# Sheet1.net
KiCad netlist of a schematic drawn in Altium Designer
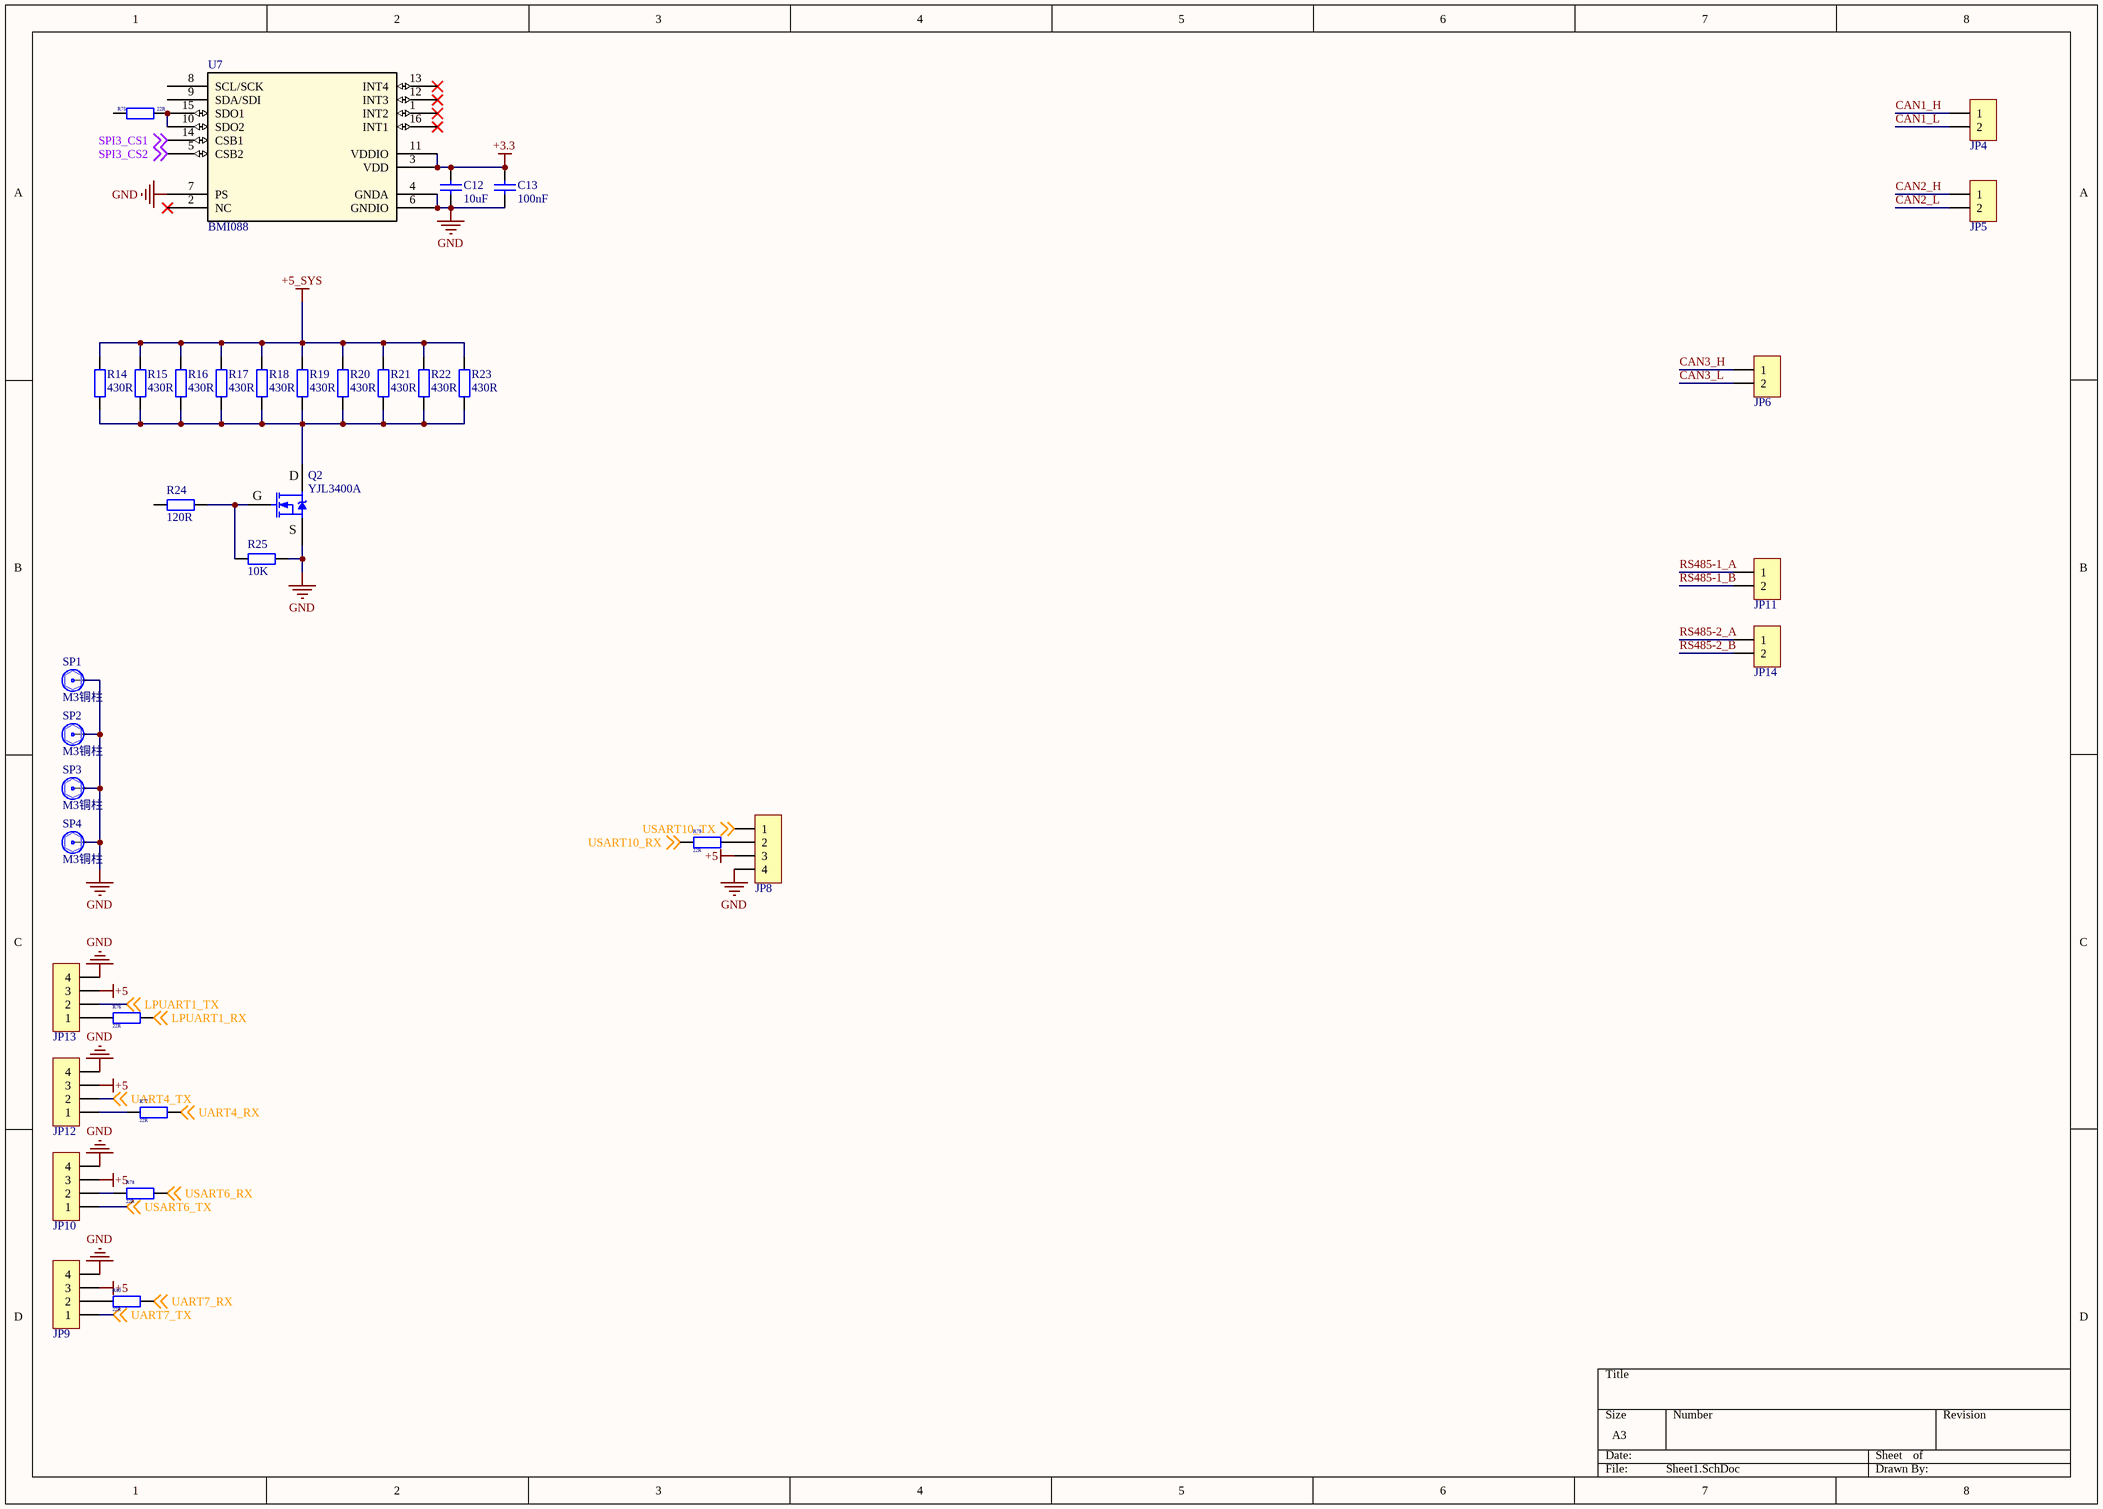
[diagram p0: Sheet1.SchDoc]

(export (version "E")
  (design (tool "Eeschema 10.0.6"))
  (components
    (comp (ref "C12")
      (value "10uF")
      (footprint "C0402_M")
      (description "贴片电容/MLCC电容")
      (libsource (lib "海南大学MECHA战队") (part "C-EDLC"))
    )
    (comp (ref "C13")
      (value "100nF")
      (footprint "C0402_M")
      (description "贴片电容/MLCC电容")
      (libsource (lib "海南大学MECHA战队") (part "C-EDLC"))
    )
    (comp (ref "JP4")
      (value "HDR-1X2")
      (footprint "GH1.25-LT-2P")
      (description "2P连接器")
      (libsource (lib "5.1 - 1.25mm连接器(FPC1.25_GH1.25_MX1.25)") (part "Header 2"))
    )
    (comp (ref "JP5")
      (value "HDR-1X2")
      (footprint "GH1.25-LT-2P")
      (description "2P连接器")
      (libsource (lib "5.1 - 1.25mm连接器(FPC1.25_GH1.25_MX1.25)") (part "Header 2"))
    )
    (comp (ref "JP6")
      (value "HDR-1X2")
      (footprint "GH1.25-LT-2P")
      (description "2P连接器")
      (libsource (lib "5.1 - 1.25mm连接器(FPC1.25_GH1.25_MX1.25)") (part "Header 2"))
    )
    (comp (ref "JP8")
      (value "HDR-1X4")
      (footprint "GH1.25-LT-4P")
      (description "4P连接器")
      (libsource (lib "5.1 - 1.25mm连接器(FPC1.25_GH1.25_MX1.25)") (part "Header 4"))
    )
    (comp (ref "JP9")
      (value "HDR-1X4")
      (footprint "GH1.25-LT-4P")
      (description "4P连接器")
      (libsource (lib "") (part "Header 4_1"))
    )
    (comp (ref "JP10")
      (value "HDR-1X4")
      (footprint "GH1.25-LT-4P")
      (description "4P连接器")
      (libsource (lib "") (part "Header 4_1"))
    )
    (comp (ref "JP11")
      (value "HDR-1X2")
      (footprint "GH1.25-LT-2P")
      (description "2P连接器")
      (libsource (lib "5.1 - 1.25mm连接器(FPC1.25_GH1.25_MX1.25)") (part "Header 2"))
    )
    (comp (ref "JP12")
      (value "HDR-1X4")
      (footprint "GH1.25-LT-4P")
      (description "4P连接器")
      (libsource (lib "") (part "Header 4_1"))
    )
    (comp (ref "JP13")
      (value "HDR-1X4")
      (footprint "GH1.25-LT-4P")
      (description "4P连接器")
      (libsource (lib "") (part "Header 4_1"))
    )
    (comp (ref "JP14")
      (value "HDR-1X2")
      (footprint "GH1.25-LT-2P")
      (description "2P连接器")
      (libsource (lib "5.1 - 1.25mm连接器(FPC1.25_GH1.25_MX1.25)") (part "Header 2"))
    )
    (comp (ref "Q2")
      (value "YJL3400A")
      (footprint "SOT23-3L")
      (description "N沟道 30V/3.16A")
      (libsource (lib "0.4 - 三极管-场效应管-可控硅") (part "SI2306"))
    )
    (comp (ref "R14")
      (value "430R")
      (footprint "R0402_M")
      (description "贴片电阻")
      (libsource (lib "海南大学MECHA战队") (part "R-High Precision"))
    )
    (comp (ref "R15")
      (value "430R")
      (footprint "R0402_M")
      (description "贴片电阻")
      (libsource (lib "海南大学MECHA战队") (part "R-High Precision"))
    )
    (comp (ref "R16")
      (value "430R")
      (footprint "R0402_M")
      (description "贴片电阻")
      (libsource (lib "海南大学MECHA战队") (part "R-High Precision"))
    )
    (comp (ref "R17")
      (value "430R")
      (footprint "R0402_M")
      (description "贴片电阻")
      (libsource (lib "海南大学MECHA战队") (part "R-High Precision"))
    )
    (comp (ref "R18")
      (value "430R")
      (footprint "R0402_M")
      (description "贴片电阻")
      (libsource (lib "海南大学MECHA战队") (part "R-High Precision"))
    )
    (comp (ref "R19")
      (value "430R")
      (footprint "R0402_M")
      (description "贴片电阻")
      (libsource (lib "海南大学MECHA战队") (part "R-High Precision"))
    )
    (comp (ref "R20")
      (value "430R")
      (footprint "R0402_M")
      (description "贴片电阻")
      (libsource (lib "海南大学MECHA战队") (part "R-High Precision"))
    )
    (comp (ref "R21")
      (value "430R")
      (footprint "R0402_M")
      (description "贴片电阻")
      (libsource (lib "海南大学MECHA战队") (part "R-High Precision"))
    )
    (comp (ref "R22")
      (value "430R")
      (footprint "R0402_M")
      (description "贴片电阻")
      (libsource (lib "海南大学MECHA战队") (part "R-High Precision"))
    )
    (comp (ref "R23")
      (value "430R")
      (footprint "R0402_M")
      (description "贴片电阻")
      (libsource (lib "海南大学MECHA战队") (part "R-High Precision"))
    )
    (comp (ref "R24")
      (value "120R")
      (footprint "R0402_M")
      (description "贴片电阻")
      (libsource (lib "海南大学MECHA战队") (part "R-High Precision"))
    )
    (comp (ref "R25")
      (value "10K")
      (footprint "R0402_M")
      (description "贴片电阻")
      (libsource (lib "海南大学MECHA战队") (part "R-High Precision"))
    )
    (comp (ref "R75")
      (value "22R")
      (footprint "R0402_M")
      (description "贴片电阻")
      (libsource (lib "0.1 - 电阻-电容-电感-保险丝-晶振-晶体-磁珠-电位器-法拉电容-馈通电容") (part "R"))
    )
    (comp (ref "R76")
      (value "22R")
      (footprint "R0402_M")
      (description "贴片电阻")
      (libsource (lib "0.1 - 电阻-电容-电感-保险丝-晶振-晶体-磁珠-电位器-法拉电容-馈通电容") (part "R"))
    )
    (comp (ref "R77")
      (value "22R")
      (footprint "R0402_M")
      (description "贴片电阻")
      (libsource (lib "0.1 - 电阻-电容-电感-保险丝-晶振-晶体-磁珠-电位器-法拉电容-馈通电容") (part "R"))
    )
    (comp (ref "R78")
      (value "22R")
      (footprint "R0402_M")
      (description "贴片电阻")
      (libsource (lib "0.1 - 电阻-电容-电感-保险丝-晶振-晶体-磁珠-电位器-法拉电容-馈通电容") (part "R"))
    )
    (comp (ref "R79")
      (value "22R")
      (footprint "R0402_M")
      (description "贴片电阻")
      (libsource (lib "0.1 - 电阻-电容-电感-保险丝-晶振-晶体-磁珠-电位器-法拉电容-馈通电容") (part "R"))
    )
    (comp (ref "R80")
      (value "22R")
      (footprint "R0402_M")
      (description "贴片电阻")
      (libsource (lib "0.1 - 电阻-电容-电感-保险丝-晶振-晶体-磁珠-电位器-法拉电容-馈通电容") (part "R"))
    )
    (comp (ref "SP1")
      (value "M3铜柱")
      (footprint "M3x4+6_N")
      (description "铜柱")
      (libsource (lib "0.5 - 按键_开关_蜂鸣器_电池_测试点_Mark点_铜柱") (part "铜柱加头大焊盘"))
    )
    (comp (ref "SP2")
      (value "M3铜柱")
      (footprint "M3x4+6_N")
      (description "铜柱")
      (libsource (lib "0.5 - 按键_开关_蜂鸣器_电池_测试点_Mark点_铜柱") (part "铜柱加头大焊盘"))
    )
    (comp (ref "SP3")
      (value "M3铜柱")
      (footprint "M3x4+6_N")
      (description "铜柱")
      (libsource (lib "0.5 - 按键_开关_蜂鸣器_电池_测试点_Mark点_铜柱") (part "铜柱加头大焊盘"))
    )
    (comp (ref "SP4")
      (value "M3铜柱")
      (footprint "M3x4+6_N")
      (description "铜柱")
      (libsource (lib "0.5 - 按键_开关_蜂鸣器_电池_测试点_Mark点_铜柱") (part "铜柱加头大焊盘"))
    )
    (comp (ref "U7")
      (value "BMI088")
      (footprint "QFN_BMI085_BOS")
      (description "BMI088 Series 3.6 V 6 Axis Digital Output Accelerometer Motion Sensor - LGA-16")
      (libsource (lib "海南大学MECHA战队") (part "BMI088-Symbol-1"))
    )
  )
  (nets
    (net (code "1") (name "+3.3") (class "Default")
      (node (ref "C12") (pin "1") (pinfunction "1_1") (pintype "passive"))
      (node (ref "C13") (pin "1") (pinfunction "1_1") (pintype "passive"))
      (node (ref "U7") (pin "11") (pinfunction "VDDIO_11") (pintype "power_in"))
      (node (ref "U7") (pin "3") (pinfunction "VDD_3") (pintype "power_in"))
    )
    (net (code "2") (name "+5") (class "Default")
      (node (ref "JP10") (pin "3") (pinfunction "3_3") (pintype "passive"))
      (node (ref "JP12") (pin "3") (pinfunction "3_3") (pintype "passive"))
      (node (ref "JP13") (pin "3") (pinfunction "3_3") (pintype "passive"))
      (node (ref "JP8") (pin "3") (pinfunction "3_3") (pintype "passive"))
      (node (ref "JP9") (pin "3") (pinfunction "3_3") (pintype "passive"))
    )
    (net (code "3") (name "+5_SYS") (class "Default")
      (node (ref "R14") (pin "2") (pinfunction "2_2") (pintype "passive"))
      (node (ref "R15") (pin "2") (pinfunction "2_2") (pintype "passive"))
      (node (ref "R16") (pin "2") (pinfunction "2_2") (pintype "passive"))
      (node (ref "R17") (pin "2") (pinfunction "2_2") (pintype "passive"))
      (node (ref "R18") (pin "2") (pinfunction "2_2") (pintype "passive"))
      (node (ref "R19") (pin "2") (pinfunction "2_2") (pintype "passive"))
      (node (ref "R20") (pin "2") (pinfunction "2_2") (pintype "passive"))
      (node (ref "R21") (pin "2") (pinfunction "2_2") (pintype "passive"))
      (node (ref "R22") (pin "2") (pinfunction "2_2") (pintype "passive"))
      (node (ref "R23") (pin "2") (pinfunction "2_2") (pintype "passive"))
    )
    (net (code "4") (name "/CAN1_H") (class "Default")
      (node (ref "JP4") (pin "1") (pinfunction "1_1") (pintype "passive"))
    )
    (net (code "5") (name "/CAN1_L") (class "Default")
      (node (ref "JP4") (pin "2") (pinfunction "2_2") (pintype "passive"))
    )
    (net (code "6") (name "/CAN2_H") (class "Default")
      (node (ref "JP5") (pin "1") (pinfunction "1_1") (pintype "passive"))
    )
    (net (code "7") (name "/CAN2_L") (class "Default")
      (node (ref "JP5") (pin "2") (pinfunction "2_2") (pintype "passive"))
    )
    (net (code "8") (name "/CAN3_H") (class "Default")
      (node (ref "JP6") (pin "1") (pinfunction "1_1") (pintype "passive"))
    )
    (net (code "9") (name "/CAN3_L") (class "Default")
      (node (ref "JP6") (pin "2") (pinfunction "2_2") (pintype "passive"))
    )
    (net (code "10") (name "/RS485-1_A") (class "Default")
      (node (ref "JP11") (pin "1") (pinfunction "1_1") (pintype "passive"))
    )
    (net (code "11") (name "/RS485-1_B") (class "Default")
      (node (ref "JP11") (pin "2") (pinfunction "2_2") (pintype "passive"))
    )
    (net (code "12") (name "/RS485-2_A") (class "Default")
      (node (ref "JP14") (pin "1") (pinfunction "1_1") (pintype "passive"))
    )
    (net (code "13") (name "/RS485-2_B") (class "Default")
      (node (ref "JP14") (pin "2") (pinfunction "2_2") (pintype "passive"))
    )
    (net (code "14") (name "GND") (class "Default")
      (node (ref "C12") (pin "2") (pinfunction "2_2") (pintype "passive"))
      (node (ref "C13") (pin "2") (pinfunction "2_2") (pintype "passive"))
      (node (ref "JP10") (pin "4") (pinfunction "4_4") (pintype "passive"))
      (node (ref "JP12") (pin "4") (pinfunction "4_4") (pintype "passive"))
      (node (ref "JP13") (pin "4") (pinfunction "4_4") (pintype "passive"))
      (node (ref "JP8") (pin "4") (pinfunction "4_4") (pintype "passive"))
      (node (ref "JP9") (pin "4") (pinfunction "4_4") (pintype "passive"))
      (node (ref "Q2") (pin "2") (pinfunction "S_2") (pintype "passive"))
      (node (ref "R25") (pin "1") (pinfunction "1_1") (pintype "passive"))
      (node (ref "SP1") (pin "1") (pinfunction "1_1") (pintype "passive"))
      (node (ref "SP2") (pin "1") (pinfunction "1_1") (pintype "passive"))
      (node (ref "SP3") (pin "1") (pinfunction "1_1") (pintype "passive"))
      (node (ref "SP4") (pin "1") (pinfunction "1_1") (pintype "passive"))
      (node (ref "U7") (pin "4") (pinfunction "GNDA_4") (pintype "power_in"))
      (node (ref "U7") (pin "6") (pinfunction "GNDIO_6") (pintype "power_in"))
      (node (ref "U7") (pin "7") (pinfunction "PS_7") (pintype "passive"))
    )
    (net (code "15") (name "LPUART1_RX") (class "Default")
      (node (ref "R76") (pin "2") (pinfunction "2_2") (pintype "passive"))
    )
    (net (code "16") (name "LPUART1_TX") (class "Default")
      (node (ref "JP13") (pin "2") (pinfunction "2_2") (pintype "passive"))
    )
    (net (code "17") (name "Net-(JP8-Pad2)") (class "Default")
      (node (ref "JP8") (pin "2") (pinfunction "2_2") (pintype "passive"))
      (node (ref "R79") (pin "2") (pinfunction "2_2") (pintype "passive"))
    )
    (net (code "18") (name "Net-(JP9-Pad2)") (class "Default")
      (node (ref "JP9") (pin "2") (pinfunction "2_2") (pintype "passive"))
      (node (ref "R80") (pin "1") (pinfunction "1_1") (pintype "passive"))
    )
    (net (code "19") (name "Net-(JP10-Pad2)") (class "Default")
      (node (ref "JP10") (pin "2") (pinfunction "2_2") (pintype "passive"))
      (node (ref "R78") (pin "1") (pinfunction "1_1") (pintype "passive"))
    )
    (net (code "20") (name "Net-(JP12-Pad1)") (class "Default")
      (node (ref "JP12") (pin "1") (pinfunction "1_1") (pintype "passive"))
      (node (ref "R77") (pin "1") (pinfunction "1_1") (pintype "passive"))
    )
    (net (code "21") (name "Net-(JP13-Pad1)") (class "Default")
      (node (ref "JP13") (pin "1") (pinfunction "1_1") (pintype "passive"))
      (node (ref "R76") (pin "1") (pinfunction "1_1") (pintype "passive"))
    )
    (net (code "22") (name "Net-(Q2-D)") (class "Default")
      (node (ref "Q2") (pin "3") (pinfunction "D_3") (pintype "passive"))
      (node (ref "R14") (pin "1") (pinfunction "1_1") (pintype "passive"))
      (node (ref "R15") (pin "1") (pinfunction "1_1") (pintype "passive"))
      (node (ref "R16") (pin "1") (pinfunction "1_1") (pintype "passive"))
      (node (ref "R17") (pin "1") (pinfunction "1_1") (pintype "passive"))
      (node (ref "R18") (pin "1") (pinfunction "1_1") (pintype "passive"))
      (node (ref "R19") (pin "1") (pinfunction "1_1") (pintype "passive"))
      (node (ref "R20") (pin "1") (pinfunction "1_1") (pintype "passive"))
      (node (ref "R21") (pin "1") (pinfunction "1_1") (pintype "passive"))
      (node (ref "R22") (pin "1") (pinfunction "1_1") (pintype "passive"))
      (node (ref "R23") (pin "1") (pinfunction "1_1") (pintype "passive"))
    )
    (net (code "23") (name "Net-(Q2-G)") (class "Default")
      (node (ref "Q2") (pin "1") (pinfunction "G_1") (pintype "passive"))
      (node (ref "R24") (pin "1") (pinfunction "1_1") (pintype "passive"))
      (node (ref "R25") (pin "2") (pinfunction "2_2") (pintype "passive"))
    )
    (net (code "24") (name "Net-(U7-SDO1)") (class "Default")
      (node (ref "R75") (pin "1") (pinfunction "1_1") (pintype "passive"))
      (node (ref "U7") (pin "10") (pinfunction "SDO2_10") (pintype "bidirectional"))
      (node (ref "U7") (pin "15") (pinfunction "SDO1_15") (pintype "bidirectional"))
    )
    (net (code "25") (name "SPI3_CS1") (class "Default")
      (node (ref "U7") (pin "14") (pinfunction "CSB1_14") (pintype "bidirectional"))
    )
    (net (code "26") (name "SPI3_CS2") (class "Default")
      (node (ref "U7") (pin "5") (pinfunction "CSB2_5") (pintype "bidirectional"))
    )
    (net (code "27") (name "UART4_RX") (class "Default")
      (node (ref "R77") (pin "2") (pinfunction "2_2") (pintype "passive"))
    )
    (net (code "28") (name "UART4_TX") (class "Default")
      (node (ref "JP12") (pin "2") (pinfunction "2_2") (pintype "passive"))
    )
    (net (code "29") (name "UART7_RX") (class "Default")
      (node (ref "R80") (pin "2") (pinfunction "2_2") (pintype "passive"))
    )
    (net (code "30") (name "UART7_TX") (class "Default")
      (node (ref "JP9") (pin "1") (pinfunction "1_1") (pintype "passive"))
    )
    (net (code "31") (name "USART6_RX") (class "Default")
      (node (ref "R78") (pin "2") (pinfunction "2_2") (pintype "passive"))
    )
    (net (code "32") (name "USART6_TX") (class "Default")
      (node (ref "JP10") (pin "1") (pinfunction "1_1") (pintype "passive"))
    )
    (net (code "33") (name "USART10_RX") (class "Default")
      (node (ref "R79") (pin "1") (pinfunction "1_1") (pintype "passive"))
    )
    (net (code "34") (name "USART10_TX") (class "Default")
      (node (ref "JP8") (pin "1") (pinfunction "1_1") (pintype "passive"))
    )
    (net (code "35") (name "unconnected-(R24-Pad2)") (class "Default")
      (node (ref "R24") (pin "2") (pinfunction "2_2") (pintype "passive"))
    )
    (net (code "36") (name "unconnected-(R75-Pad2)") (class "Default")
      (node (ref "R75") (pin "2") (pinfunction "2_2") (pintype "passive"))
    )
    (net (code "37") (name "unconnected-(U7-INT1-Pad16)") (class "Default")
      (node (ref "U7") (pin "16") (pinfunction "INT1_16") (pintype "bidirectional+no_connect"))
    )
    (net (code "38") (name "unconnected-(U7-INT2-Pad1)") (class "Default")
      (node (ref "U7") (pin "1") (pinfunction "INT2_1") (pintype "bidirectional+no_connect"))
    )
    (net (code "39") (name "unconnected-(U7-INT3-Pad12)") (class "Default")
      (node (ref "U7") (pin "12") (pinfunction "INT3_12") (pintype "bidirectional+no_connect"))
    )
    (net (code "40") (name "unconnected-(U7-INT4-Pad13)") (class "Default")
      (node (ref "U7") (pin "13") (pinfunction "INT4_13") (pintype "bidirectional+no_connect"))
    )
    (net (code "41") (name "unconnected-(U7-NC-Pad2)") (class "Default")
      (node (ref "U7") (pin "2") (pinfunction "NC_2") (pintype "passive+no_connect"))
    )
    (net (code "42") (name "unconnected-(U7-SCL{slash}SCK-Pad8)") (class "Default")
      (node (ref "U7") (pin "8") (pinfunction "SCL/SCK_8") (pintype "passive"))
    )
    (net (code "43") (name "unconnected-(U7-SDA{slash}SDI-Pad9)") (class "Default")
      (node (ref "U7") (pin "9") (pinfunction "SDA/SDI_9") (pintype "passive"))
    )
  )
)
